# MODUL_RELAIS_8_V101.net
KiCad netlist of a schematic drawn in EAGLE
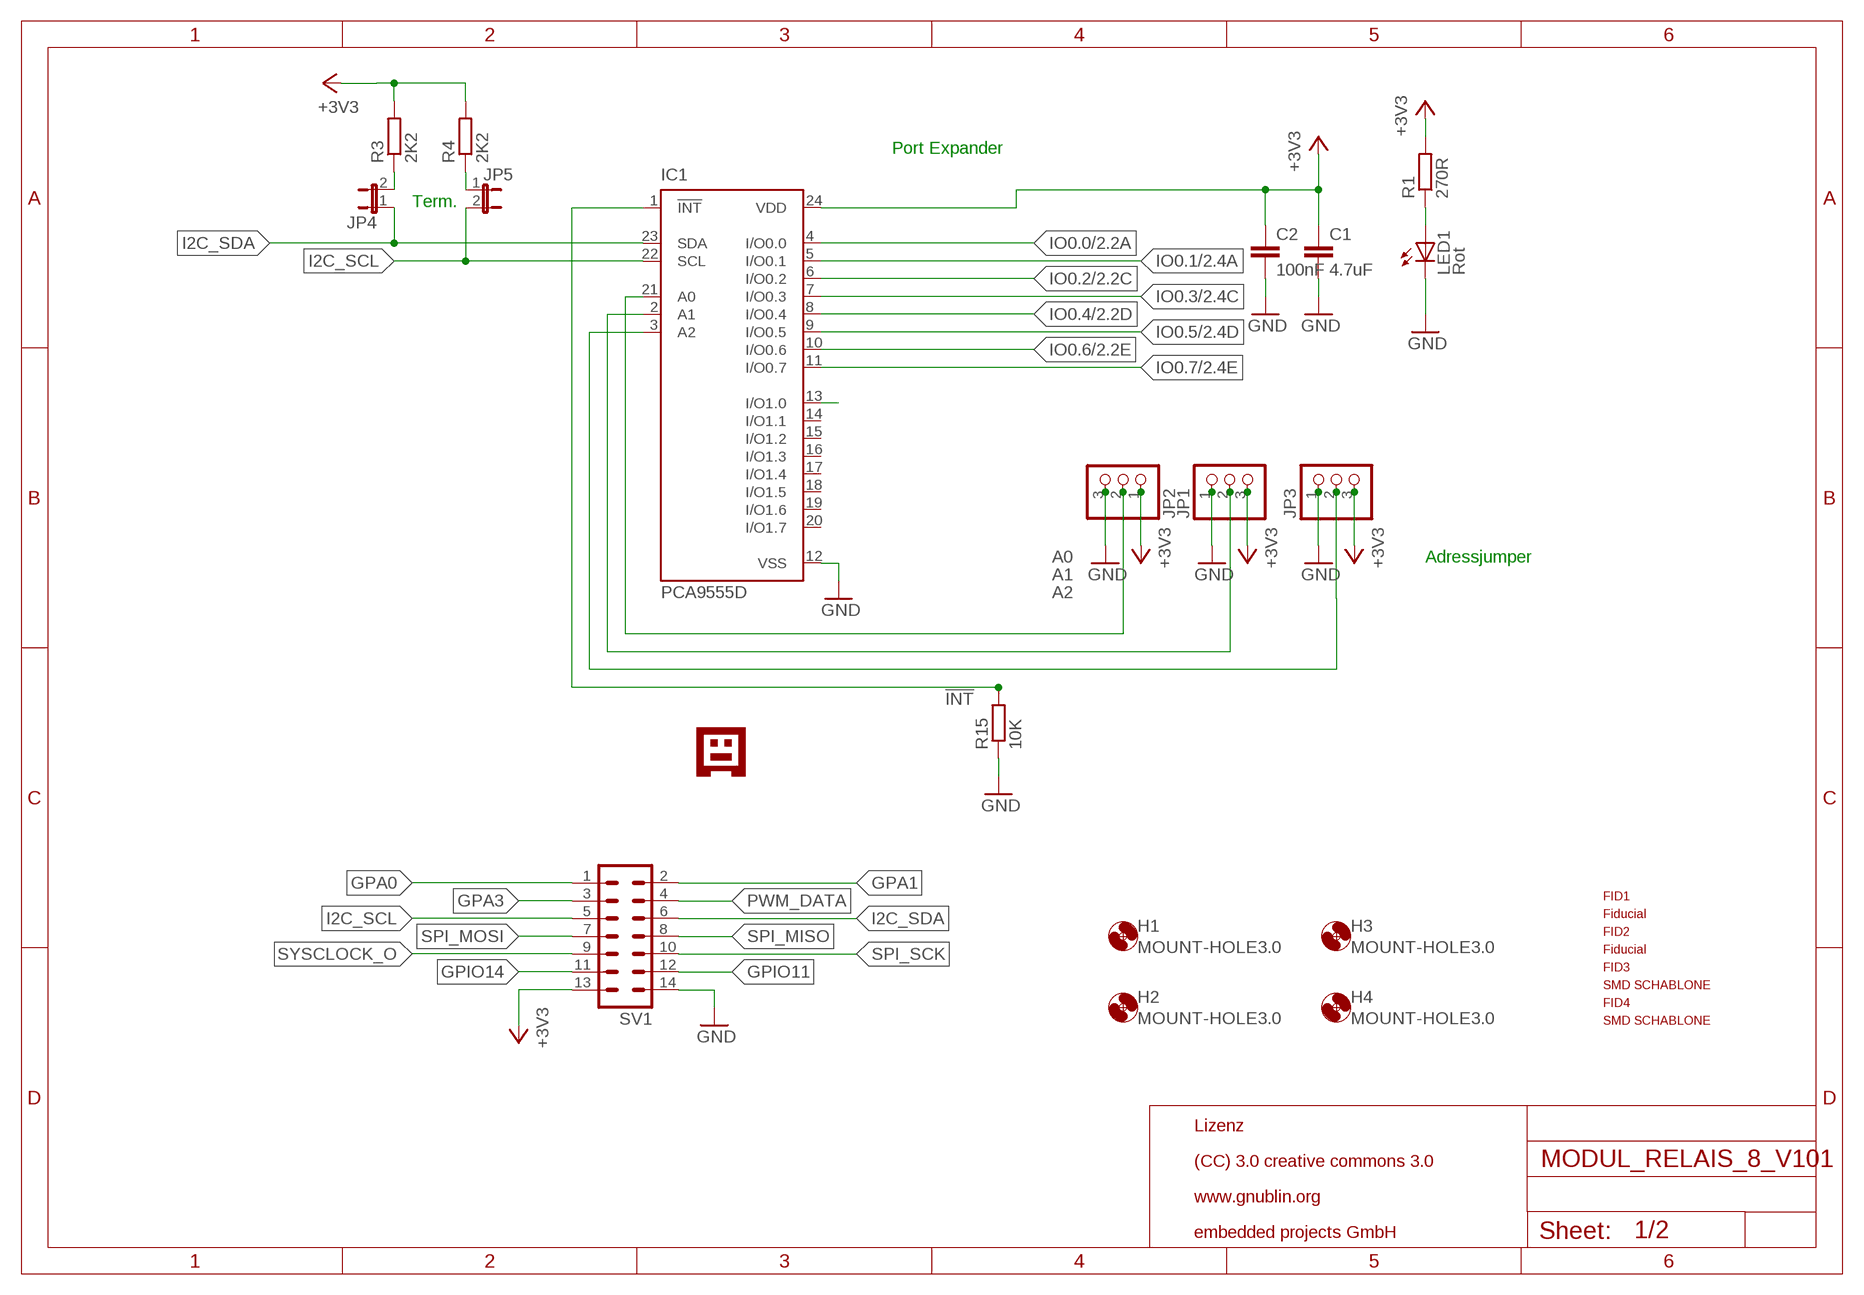
[diagram p0: schematic, sheet 1]
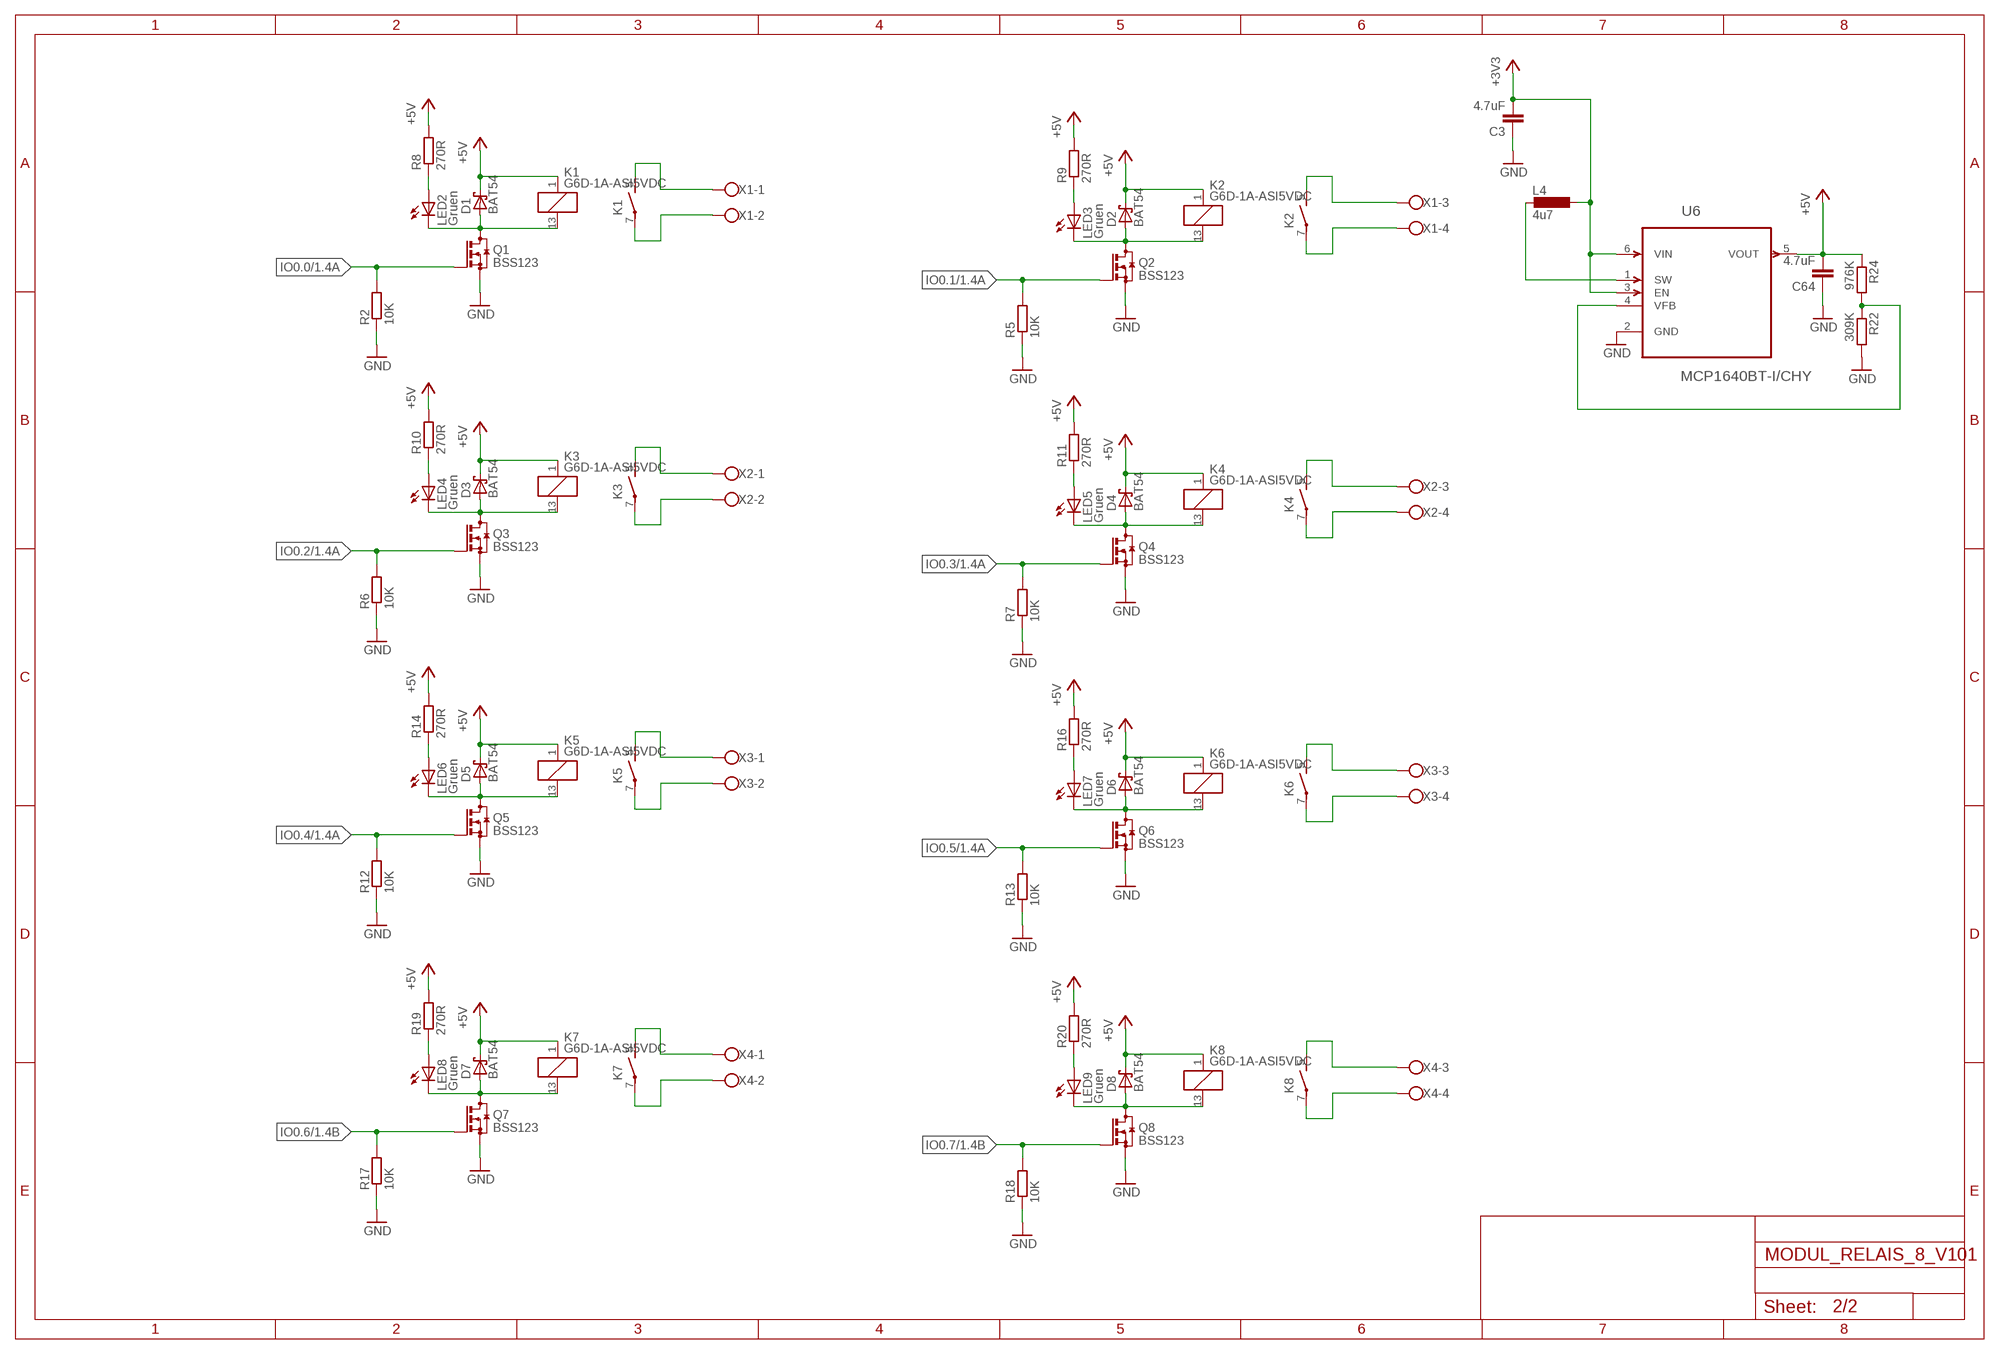
[diagram p1: schematic, sheet 2]

(export (version "E")
  (design (tool "Eeschema 10.0.6"))
  (components
    (comp (ref "C1")
      (value "4.7uF")
      (footprint "eagle-import:C0805")
      (libsource (lib "eagle-import") (part "C-EUC0805"))
    )
    (comp (ref "C2")
      (value "100nF")
      (footprint "eagle-import:C0805")
      (libsource (lib "eagle-import") (part "C-EUC0805"))
    )
    (comp (ref "FID1")
      (value "PASSERMARKEN_FIDUCIAL")
      (footprint "eagle-import:PASSERMARKEN_FIDUCIAL")
      (libsource (lib "eagle-import") (part "PASSERMARKEN_FIDUCIAL"))
    )
    (comp (ref "FID2")
      (value "PASSERMARKEN_FIDUCIAL")
      (footprint "eagle-import:PASSERMARKEN_FIDUCIAL")
      (libsource (lib "eagle-import") (part "PASSERMARKEN_FIDUCIAL"))
    )
    (comp (ref "FID3")
      (value "PASSERMARKEN_FIDUCIAL")
      (footprint "eagle-import:PASSERMARKEN_FIDUCIAL")
      (libsource (lib "eagle-import") (part "SMDSCHABLONE_PASSERMARKEN_FIDUCIAL"))
    )
    (comp (ref "FID4")
      (value "PASSERMARKEN_FIDUCIAL")
      (footprint "eagle-import:PASSERMARKEN_FIDUCIAL")
      (libsource (lib "eagle-import") (part "SMDSCHABLONE_PASSERMARKEN_FIDUCIAL"))
    )
    (comp (ref "H1")
      (value "MOUNT-HOLE3.0")
      (footprint "eagle-import:3,0")
      (libsource (lib "eagle-import") (part "MOUNT-HOLE3.0"))
    )
    (comp (ref "H2")
      (value "MOUNT-HOLE3.0")
      (footprint "eagle-import:3,0")
      (libsource (lib "eagle-import") (part "MOUNT-HOLE3.0"))
    )
    (comp (ref "H3")
      (value "MOUNT-HOLE3.0")
      (footprint "eagle-import:3,0")
      (libsource (lib "eagle-import") (part "MOUNT-HOLE3.0"))
    )
    (comp (ref "H4")
      (value "MOUNT-HOLE3.0")
      (footprint "eagle-import:3,0")
      (libsource (lib "eagle-import") (part "MOUNT-HOLE3.0"))
    )
    (comp (ref "IC1")
      (value "PCA9555D")
      (footprint "eagle-import:SO24")
      (fields (field (name "MPN") "PCA9555DW") (field (name "OC_FARNELL") "8906076"))
      (libsource (lib "eagle-import") (part "PCA9555D"))
    )
    (comp (ref "JP1")
      (value "PINHD-1X3")
      (footprint "eagle-import:1X03")
      (libsource (lib "eagle-import") (part "PINHD-1X3"))
    )
    (comp (ref "JP2")
      (value "PINHD-1X3")
      (footprint "eagle-import:1X03")
      (libsource (lib "eagle-import") (part "PINHD-1X3"))
    )
    (comp (ref "JP3")
      (value "PINHD-1X3")
      (footprint "eagle-import:1X03")
      (libsource (lib "eagle-import") (part "PINHD-1X3"))
    )
    (comp (ref "JP4")
      (value "JP1E")
      (footprint "eagle-import:JP1")
      (libsource (lib "eagle-import") (part "JP1E"))
    )
    (comp (ref "JP5")
      (value "JP1E")
      (footprint "eagle-import:JP1")
      (libsource (lib "eagle-import") (part "JP1E"))
    )
    (comp (ref "LED1")
      (value "Rot")
      (footprint "eagle-import:CHIP-LED0805")
      (libsource (lib "eagle-import") (part "LEDCHIP-LED0805"))
    )
    (comp (ref "R1")
      (value "270R")
      (footprint "eagle-import:R0805")
      (libsource (lib "eagle-import") (part "R-EU_R0805"))
    )
    (comp (ref "R3")
      (value "2K2")
      (footprint "eagle-import:R0805")
      (libsource (lib "eagle-import") (part "R-EU_R0805"))
    )
    (comp (ref "R4")
      (value "2K2")
      (footprint "eagle-import:R0805")
      (libsource (lib "eagle-import") (part "R-EU_R0805"))
    )
    (comp (ref "R15")
      (value "10K")
      (footprint "eagle-import:R0805")
      (libsource (lib "eagle-import") (part "R-EU_R0805"))
    )
    (comp (ref "SV1")
      (value "ML14")
      (footprint "eagle-import:ML14")
      (libsource (lib "eagle-import") (part "ML14"))
    )
    (comp (ref "U$1")
      (value "GNUBLINLOGOSIEB")
      (footprint "eagle-import:GNUSIEBDRUCK")
      (libsource (lib "eagle-import") (part "GNUBLINLOGOSIEB"))
    )
    (comp (ref "C3")
      (value "4.7uF")
      (footprint "eagle-import:C0805")
      (libsource (lib "eagle-import") (part "C-EUC0805"))
    )
    (comp (ref "C64")
      (value "4.7uF")
      (footprint "eagle-import:C0805")
      (libsource (lib "eagle-import") (part "C-EUC0805"))
    )
    (comp (ref "D1")
      (value "BAT54")
      (footprint "eagle-import:DIODE_SOT23")
      (libsource (lib "eagle-import") (part "DIODE_BAT54"))
    )
    (comp (ref "D2")
      (value "BAT54")
      (footprint "eagle-import:DIODE_SOT23")
      (libsource (lib "eagle-import") (part "DIODE_BAT54"))
    )
    (comp (ref "D3")
      (value "BAT54")
      (footprint "eagle-import:DIODE_SOT23")
      (libsource (lib "eagle-import") (part "DIODE_BAT54"))
    )
    (comp (ref "D4")
      (value "BAT54")
      (footprint "eagle-import:DIODE_SOT23")
      (libsource (lib "eagle-import") (part "DIODE_BAT54"))
    )
    (comp (ref "D5")
      (value "BAT54")
      (footprint "eagle-import:DIODE_SOT23")
      (libsource (lib "eagle-import") (part "DIODE_BAT54"))
    )
    (comp (ref "D6")
      (value "BAT54")
      (footprint "eagle-import:DIODE_SOT23")
      (libsource (lib "eagle-import") (part "DIODE_BAT54"))
    )
    (comp (ref "D7")
      (value "BAT54")
      (footprint "eagle-import:DIODE_SOT23")
      (libsource (lib "eagle-import") (part "DIODE_BAT54"))
    )
    (comp (ref "D8")
      (value "BAT54")
      (footprint "eagle-import:DIODE_SOT23")
      (libsource (lib "eagle-import") (part "DIODE_BAT54"))
    )
    (comp (ref "K1")
      (value "G6D-1A-ASI5VDC")
      (footprint "eagle-import:RELAY_G6D")
      (libsource (lib "eagle-import") (part "RELAY_G6D?-1A-ASI5VDC"))
    )
    (comp (ref "K2")
      (value "G6D-1A-ASI5VDC")
      (footprint "eagle-import:RELAY_G6D")
      (libsource (lib "eagle-import") (part "RELAY_G6D?-1A-ASI5VDC"))
    )
    (comp (ref "K3")
      (value "G6D-1A-ASI5VDC")
      (footprint "eagle-import:RELAY_G6D")
      (libsource (lib "eagle-import") (part "RELAY_G6D?-1A-ASI5VDC"))
    )
    (comp (ref "K4")
      (value "G6D-1A-ASI5VDC")
      (footprint "eagle-import:RELAY_G6D")
      (libsource (lib "eagle-import") (part "RELAY_G6D?-1A-ASI5VDC"))
    )
    (comp (ref "K5")
      (value "G6D-1A-ASI5VDC")
      (footprint "eagle-import:RELAY_G6D")
      (libsource (lib "eagle-import") (part "RELAY_G6D?-1A-ASI5VDC"))
    )
    (comp (ref "K6")
      (value "G6D-1A-ASI5VDC")
      (footprint "eagle-import:RELAY_G6D")
      (libsource (lib "eagle-import") (part "RELAY_G6D?-1A-ASI5VDC"))
    )
    (comp (ref "K7")
      (value "G6D-1A-ASI5VDC")
      (footprint "eagle-import:RELAY_G6D")
      (libsource (lib "eagle-import") (part "RELAY_G6D?-1A-ASI5VDC"))
    )
    (comp (ref "K8")
      (value "G6D-1A-ASI5VDC")
      (footprint "eagle-import:RELAY_G6D")
      (libsource (lib "eagle-import") (part "RELAY_G6D?-1A-ASI5VDC"))
    )
    (comp (ref "L4")
      (value "4u7")
      (footprint "eagle-import:PSU3014")
      (libsource (lib "eagle-import") (part "PSU3014"))
    )
    (comp (ref "LED2")
      (value "Gruen")
      (footprint "eagle-import:CHIP-LED0805")
      (libsource (lib "eagle-import") (part "LEDCHIP-LED0805"))
    )
    (comp (ref "LED3")
      (value "Gruen")
      (footprint "eagle-import:CHIP-LED0805")
      (libsource (lib "eagle-import") (part "LEDCHIP-LED0805"))
    )
    (comp (ref "LED4")
      (value "Gruen")
      (footprint "eagle-import:CHIP-LED0805")
      (libsource (lib "eagle-import") (part "LEDCHIP-LED0805"))
    )
    (comp (ref "LED5")
      (value "Gruen")
      (footprint "eagle-import:CHIP-LED0805")
      (libsource (lib "eagle-import") (part "LEDCHIP-LED0805"))
    )
    (comp (ref "LED6")
      (value "Gruen")
      (footprint "eagle-import:CHIP-LED0805")
      (libsource (lib "eagle-import") (part "LEDCHIP-LED0805"))
    )
    (comp (ref "LED7")
      (value "Gruen")
      (footprint "eagle-import:CHIP-LED0805")
      (libsource (lib "eagle-import") (part "LEDCHIP-LED0805"))
    )
    (comp (ref "LED8")
      (value "Gruen")
      (footprint "eagle-import:CHIP-LED0805")
      (libsource (lib "eagle-import") (part "LEDCHIP-LED0805"))
    )
    (comp (ref "LED9")
      (value "Gruen")
      (footprint "eagle-import:CHIP-LED0805")
      (libsource (lib "eagle-import") (part "LEDCHIP-LED0805"))
    )
    (comp (ref "Q1")
      (value "BSS123")
      (footprint "eagle-import:TRANSISTOR-SMALL-SIGNAL_SOT23")
      (libsource (lib "eagle-import") (part "TRANSISTOR-SMALL-SIGNAL_BSS123"))
    )
    (comp (ref "Q2")
      (value "BSS123")
      (footprint "eagle-import:TRANSISTOR-SMALL-SIGNAL_SOT23")
      (libsource (lib "eagle-import") (part "TRANSISTOR-SMALL-SIGNAL_BSS123"))
    )
    (comp (ref "Q3")
      (value "BSS123")
      (footprint "eagle-import:TRANSISTOR-SMALL-SIGNAL_SOT23")
      (libsource (lib "eagle-import") (part "TRANSISTOR-SMALL-SIGNAL_BSS123"))
    )
    (comp (ref "Q4")
      (value "BSS123")
      (footprint "eagle-import:TRANSISTOR-SMALL-SIGNAL_SOT23")
      (libsource (lib "eagle-import") (part "TRANSISTOR-SMALL-SIGNAL_BSS123"))
    )
    (comp (ref "Q5")
      (value "BSS123")
      (footprint "eagle-import:TRANSISTOR-SMALL-SIGNAL_SOT23")
      (libsource (lib "eagle-import") (part "TRANSISTOR-SMALL-SIGNAL_BSS123"))
    )
    (comp (ref "Q6")
      (value "BSS123")
      (footprint "eagle-import:TRANSISTOR-SMALL-SIGNAL_SOT23")
      (libsource (lib "eagle-import") (part "TRANSISTOR-SMALL-SIGNAL_BSS123"))
    )
    (comp (ref "Q7")
      (value "BSS123")
      (footprint "eagle-import:TRANSISTOR-SMALL-SIGNAL_SOT23")
      (libsource (lib "eagle-import") (part "TRANSISTOR-SMALL-SIGNAL_BSS123"))
    )
    (comp (ref "Q8")
      (value "BSS123")
      (footprint "eagle-import:TRANSISTOR-SMALL-SIGNAL_SOT23")
      (libsource (lib "eagle-import") (part "TRANSISTOR-SMALL-SIGNAL_BSS123"))
    )
    (comp (ref "R2")
      (value "10K")
      (footprint "eagle-import:R0805")
      (libsource (lib "eagle-import") (part "R-EU_R0805"))
    )
    (comp (ref "R5")
      (value "10K")
      (footprint "eagle-import:R0805")
      (libsource (lib "eagle-import") (part "R-EU_R0805"))
    )
    (comp (ref "R6")
      (value "10K")
      (footprint "eagle-import:R0805")
      (libsource (lib "eagle-import") (part "R-EU_R0805"))
    )
    (comp (ref "R7")
      (value "10K")
      (footprint "eagle-import:R0805")
      (libsource (lib "eagle-import") (part "R-EU_R0805"))
    )
    (comp (ref "R8")
      (value "270R")
      (footprint "eagle-import:R0805")
      (libsource (lib "eagle-import") (part "R-EU_R0805"))
    )
    (comp (ref "R9")
      (value "270R")
      (footprint "eagle-import:R0805")
      (libsource (lib "eagle-import") (part "R-EU_R0805"))
    )
    (comp (ref "R10")
      (value "270R")
      (footprint "eagle-import:R0805")
      (libsource (lib "eagle-import") (part "R-EU_R0805"))
    )
    (comp (ref "R11")
      (value "270R")
      (footprint "eagle-import:R0805")
      (libsource (lib "eagle-import") (part "R-EU_R0805"))
    )
    (comp (ref "R12")
      (value "10K")
      (footprint "eagle-import:R0805")
      (libsource (lib "eagle-import") (part "R-EU_R0805"))
    )
    (comp (ref "R13")
      (value "10K")
      (footprint "eagle-import:R0805")
      (libsource (lib "eagle-import") (part "R-EU_R0805"))
    )
    (comp (ref "R14")
      (value "270R")
      (footprint "eagle-import:R0805")
      (libsource (lib "eagle-import") (part "R-EU_R0805"))
    )
    (comp (ref "R16")
      (value "270R")
      (footprint "eagle-import:R0805")
      (libsource (lib "eagle-import") (part "R-EU_R0805"))
    )
    (comp (ref "R17")
      (value "10K")
      (footprint "eagle-import:R0805")
      (libsource (lib "eagle-import") (part "R-EU_R0805"))
    )
    (comp (ref "R18")
      (value "10K")
      (footprint "eagle-import:R0805")
      (libsource (lib "eagle-import") (part "R-EU_R0805"))
    )
    (comp (ref "R19")
      (value "270R")
      (footprint "eagle-import:R0805")
      (libsource (lib "eagle-import") (part "R-EU_R0805"))
    )
    (comp (ref "R20")
      (value "270R")
      (footprint "eagle-import:R0805")
      (libsource (lib "eagle-import") (part "R-EU_R0805"))
    )
    (comp (ref "R22")
      (value "309K")
      (footprint "eagle-import:R0805")
      (libsource (lib "eagle-import") (part "R-EU_R0805"))
    )
    (comp (ref "R24")
      (value "976K")
      (footprint "eagle-import:R0805")
      (libsource (lib "eagle-import") (part "R-EU_R0805"))
    )
    (comp (ref "U6")
      (value "MCP1640BT-I/CHY")
      (footprint "eagle-import:SOT95P270X145-6N")
      (libsource (lib "eagle-import") (part "MCP1640BT-I/CHY"))
    )
    (comp (ref "X1")
      (value "W237-04P")
      (footprint "eagle-import:W237-4P")
      (libsource (lib "eagle-import") (part "W237-04P"))
    )
    (comp (ref "X2")
      (value "W237-04P")
      (footprint "eagle-import:W237-4P")
      (libsource (lib "eagle-import") (part "W237-04P"))
    )
    (comp (ref "X3")
      (value "W237-04P")
      (footprint "eagle-import:W237-4P")
      (libsource (lib "eagle-import") (part "W237-04P"))
    )
    (comp (ref "X4")
      (value "W237-04P")
      (footprint "eagle-import:W237-4P")
      (libsource (lib "eagle-import") (part "W237-04P"))
    )
  )
  (nets
    (net (code "1") (name "+3V3") (class "Default")
      (node (ref "C1") (pin "1") (pinfunction "1_1") (pintype "passive"))
      (node (ref "C2") (pin "1") (pinfunction "1_1") (pintype "passive"))
      (node (ref "C3") (pin "2") (pinfunction "2_2") (pintype "passive"))
      (node (ref "IC1") (pin "24") (pinfunction "VDD_24") (pintype "power_in"))
      (node (ref "JP1") (pin "3") (pinfunction "3_3") (pintype "passive"))
      (node (ref "JP2") (pin "1") (pinfunction "1_1") (pintype "passive"))
      (node (ref "JP3") (pin "3") (pinfunction "3_3") (pintype "passive"))
      (node (ref "L4") (pin "2") (pinfunction "2_2") (pintype "passive"))
      (node (ref "R1") (pin "2") (pinfunction "2_2") (pintype "passive"))
      (node (ref "R3") (pin "2") (pinfunction "2_2") (pintype "passive"))
      (node (ref "R4") (pin "2") (pinfunction "2_2") (pintype "passive"))
      (node (ref "SV1") (pin "13") (pinfunction "13_13") (pintype "passive"))
      (node (ref "U6") (pin "3") (pinfunction "EN_3") (pintype "input"))
      (node (ref "U6") (pin "6") (pinfunction "VIN_6") (pintype "input"))
    )
    (net (code "2") (name "+5V") (class "Default")
      (node (ref "C64") (pin "2") (pinfunction "2_2") (pintype "passive"))
      (node (ref "D1") (pin "3") (pinfunction "C_3") (pintype "passive"))
      (node (ref "D2") (pin "3") (pinfunction "C_3") (pintype "passive"))
      (node (ref "D3") (pin "3") (pinfunction "C_3") (pintype "passive"))
      (node (ref "D4") (pin "3") (pinfunction "C_3") (pintype "passive"))
      (node (ref "D5") (pin "3") (pinfunction "C_3") (pintype "passive"))
      (node (ref "D6") (pin "3") (pinfunction "C_3") (pintype "passive"))
      (node (ref "D7") (pin "3") (pinfunction "C_3") (pintype "passive"))
      (node (ref "D8") (pin "3") (pinfunction "C_3") (pintype "passive"))
      (node (ref "K1") (pin "1") (pinfunction "1_1") (pintype "passive"))
      (node (ref "K2") (pin "1") (pinfunction "1_1") (pintype "passive"))
      (node (ref "K3") (pin "1") (pinfunction "1_1") (pintype "passive"))
      (node (ref "K4") (pin "1") (pinfunction "1_1") (pintype "passive"))
      (node (ref "K5") (pin "1") (pinfunction "1_1") (pintype "passive"))
      (node (ref "K6") (pin "1") (pinfunction "1_1") (pintype "passive"))
      (node (ref "K7") (pin "1") (pinfunction "1_1") (pintype "passive"))
      (node (ref "K8") (pin "1") (pinfunction "1_1") (pintype "passive"))
      (node (ref "R10") (pin "2") (pinfunction "2_2") (pintype "passive"))
      (node (ref "R11") (pin "2") (pinfunction "2_2") (pintype "passive"))
      (node (ref "R14") (pin "2") (pinfunction "2_2") (pintype "passive"))
      (node (ref "R16") (pin "2") (pinfunction "2_2") (pintype "passive"))
      (node (ref "R19") (pin "2") (pinfunction "2_2") (pintype "passive"))
      (node (ref "R20") (pin "2") (pinfunction "2_2") (pintype "passive"))
      (node (ref "R24") (pin "1") (pinfunction "1_1") (pintype "passive"))
      (node (ref "R8") (pin "2") (pinfunction "2_2") (pintype "passive"))
      (node (ref "R9") (pin "2") (pinfunction "2_2") (pintype "passive"))
      (node (ref "U6") (pin "5") (pinfunction "VOUT_5") (pintype "output"))
    )
    (net (code "3") (name "A0") (class "Default")
      (node (ref "IC1") (pin "21") (pinfunction "A0_21") (pintype "input"))
      (node (ref "JP2") (pin "2") (pinfunction "2_2") (pintype "passive"))
    )
    (net (code "4") (name "A1") (class "Default")
      (node (ref "IC1") (pin "2") (pinfunction "A1_2") (pintype "input"))
      (node (ref "JP1") (pin "2") (pinfunction "2_2") (pintype "passive"))
    )
    (net (code "5") (name "A2") (class "Default")
      (node (ref "IC1") (pin "3") (pinfunction "A2_3") (pintype "input"))
      (node (ref "JP3") (pin "2") (pinfunction "2_2") (pintype "passive"))
    )
    (net (code "6") (name "GND") (class "Default")
      (node (ref "C1") (pin "2") (pinfunction "2_2") (pintype "passive"))
      (node (ref "C2") (pin "2") (pinfunction "2_2") (pintype "passive"))
      (node (ref "C3") (pin "1") (pinfunction "1_1") (pintype "passive"))
      (node (ref "C64") (pin "1") (pinfunction "1_1") (pintype "passive"))
      (node (ref "IC1") (pin "12") (pinfunction "VSS_12") (pintype "power_in"))
      (node (ref "JP1") (pin "1") (pinfunction "1_1") (pintype "passive"))
      (node (ref "JP2") (pin "3") (pinfunction "3_3") (pintype "passive"))
      (node (ref "JP3") (pin "1") (pinfunction "1_1") (pintype "passive"))
      (node (ref "LED1") (pin "C") (pinfunction "C_C") (pintype "passive"))
      (node (ref "Q1") (pin "2") (pinfunction "S_2") (pintype "passive"))
      (node (ref "Q2") (pin "2") (pinfunction "S_2") (pintype "passive"))
      (node (ref "Q3") (pin "2") (pinfunction "S_2") (pintype "passive"))
      (node (ref "Q4") (pin "2") (pinfunction "S_2") (pintype "passive"))
      (node (ref "Q5") (pin "2") (pinfunction "S_2") (pintype "passive"))
      (node (ref "Q6") (pin "2") (pinfunction "S_2") (pintype "passive"))
      (node (ref "Q7") (pin "2") (pinfunction "S_2") (pintype "passive"))
      (node (ref "Q8") (pin "2") (pinfunction "S_2") (pintype "passive"))
      (node (ref "R12") (pin "1") (pinfunction "1_1") (pintype "passive"))
      (node (ref "R13") (pin "1") (pinfunction "1_1") (pintype "passive"))
      (node (ref "R15") (pin "1") (pinfunction "1_1") (pintype "passive"))
      (node (ref "R17") (pin "1") (pinfunction "1_1") (pintype "passive"))
      (node (ref "R18") (pin "1") (pinfunction "1_1") (pintype "passive"))
      (node (ref "R2") (pin "1") (pinfunction "1_1") (pintype "passive"))
      (node (ref "R22") (pin "2") (pinfunction "2_2") (pintype "passive"))
      (node (ref "R5") (pin "1") (pinfunction "1_1") (pintype "passive"))
      (node (ref "R6") (pin "1") (pinfunction "1_1") (pintype "passive"))
      (node (ref "R7") (pin "1") (pinfunction "1_1") (pintype "passive"))
      (node (ref "SV1") (pin "14") (pinfunction "14_14") (pintype "passive"))
      (node (ref "U6") (pin "2") (pinfunction "GND_2") (pintype "passive"))
    )
    (net (code "7") (name "GPA0") (class "Default")
      (node (ref "SV1") (pin "1") (pinfunction "1_1") (pintype "passive"))
    )
    (net (code "8") (name "GPA1") (class "Default")
      (node (ref "SV1") (pin "2") (pinfunction "2_2") (pintype "passive"))
    )
    (net (code "9") (name "GPA3") (class "Default")
      (node (ref "SV1") (pin "3") (pinfunction "3_3") (pintype "passive"))
    )
    (net (code "10") (name "GPIO11") (class "Default")
      (node (ref "SV1") (pin "12") (pinfunction "12_12") (pintype "passive"))
    )
    (net (code "11") (name "GPIO14") (class "Default")
      (node (ref "SV1") (pin "11") (pinfunction "11_11") (pintype "passive"))
    )
    (net (code "12") (name "I2C_SCL") (class "Default")
      (node (ref "IC1") (pin "22") (pinfunction "SCL_22") (pintype "input"))
      (node (ref "JP5") (pin "2") (pinfunction "2_2") (pintype "passive"))
      (node (ref "SV1") (pin "5") (pinfunction "5_5") (pintype "passive"))
    )
    (net (code "13") (name "I2C_SDA") (class "Default")
      (node (ref "IC1") (pin "23") (pinfunction "SDA_23") (pintype "bidirectional"))
      (node (ref "JP4") (pin "1") (pinfunction "1_1") (pintype "passive"))
      (node (ref "SV1") (pin "6") (pinfunction "6_6") (pintype "passive"))
    )
    (net (code "14") (name "IO0.0") (class "Default")
      (node (ref "IC1") (pin "4") (pinfunction "I/O0.0_4") (pintype "bidirectional"))
      (node (ref "Q1") (pin "1") (pinfunction "G_1") (pintype "passive"))
      (node (ref "R2") (pin "2") (pinfunction "2_2") (pintype "passive"))
    )
    (net (code "15") (name "IO0.1") (class "Default")
      (node (ref "IC1") (pin "5") (pinfunction "I/O0.1_5") (pintype "bidirectional"))
      (node (ref "Q2") (pin "1") (pinfunction "G_1") (pintype "passive"))
      (node (ref "R5") (pin "2") (pinfunction "2_2") (pintype "passive"))
    )
    (net (code "16") (name "IO0.2") (class "Default")
      (node (ref "IC1") (pin "6") (pinfunction "I/O0.2_6") (pintype "bidirectional"))
      (node (ref "Q3") (pin "1") (pinfunction "G_1") (pintype "passive"))
      (node (ref "R6") (pin "2") (pinfunction "2_2") (pintype "passive"))
    )
    (net (code "17") (name "IO0.3") (class "Default")
      (node (ref "IC1") (pin "7") (pinfunction "I/O0.3_7") (pintype "bidirectional"))
      (node (ref "Q4") (pin "1") (pinfunction "G_1") (pintype "passive"))
      (node (ref "R7") (pin "2") (pinfunction "2_2") (pintype "passive"))
    )
    (net (code "18") (name "IO0.4") (class "Default")
      (node (ref "IC1") (pin "8") (pinfunction "I/O0.4_8") (pintype "bidirectional"))
      (node (ref "Q5") (pin "1") (pinfunction "G_1") (pintype "passive"))
      (node (ref "R12") (pin "2") (pinfunction "2_2") (pintype "passive"))
    )
    (net (code "19") (name "IO0.5") (class "Default")
      (node (ref "IC1") (pin "9") (pinfunction "I/O0.5_9") (pintype "bidirectional"))
      (node (ref "Q6") (pin "1") (pinfunction "G_1") (pintype "passive"))
      (node (ref "R13") (pin "2") (pinfunction "2_2") (pintype "passive"))
    )
    (net (code "20") (name "IO0.6") (class "Default")
      (node (ref "IC1") (pin "10") (pinfunction "I/O0.6_10") (pintype "bidirectional"))
      (node (ref "Q7") (pin "1") (pinfunction "G_1") (pintype "passive"))
      (node (ref "R17") (pin "2") (pinfunction "2_2") (pintype "passive"))
    )
    (net (code "21") (name "IO0.7") (class "Default")
      (node (ref "IC1") (pin "11") (pinfunction "I/O0.7_11") (pintype "bidirectional"))
      (node (ref "Q8") (pin "1") (pinfunction "G_1") (pintype "passive"))
      (node (ref "R18") (pin "2") (pinfunction "2_2") (pintype "passive"))
    )
    (net (code "22") (name "Net-(D1-A)") (class "Default")
      (node (ref "D1") (pin "1") (pinfunction "A_1") (pintype "passive"))
      (node (ref "K1") (pin "13") (pinfunction "2_13") (pintype "passive"))
      (node (ref "LED2") (pin "C") (pinfunction "C_C") (pintype "passive"))
      (node (ref "Q1") (pin "3") (pinfunction "D_3") (pintype "passive"))
    )
    (net (code "23") (name "Net-(D2-A)") (class "Default")
      (node (ref "D2") (pin "1") (pinfunction "A_1") (pintype "passive"))
      (node (ref "K2") (pin "13") (pinfunction "2_13") (pintype "passive"))
      (node (ref "LED3") (pin "C") (pinfunction "C_C") (pintype "passive"))
      (node (ref "Q2") (pin "3") (pinfunction "D_3") (pintype "passive"))
    )
    (net (code "24") (name "Net-(D3-A)") (class "Default")
      (node (ref "D3") (pin "1") (pinfunction "A_1") (pintype "passive"))
      (node (ref "K3") (pin "13") (pinfunction "2_13") (pintype "passive"))
      (node (ref "LED4") (pin "C") (pinfunction "C_C") (pintype "passive"))
      (node (ref "Q3") (pin "3") (pinfunction "D_3") (pintype "passive"))
    )
    (net (code "25") (name "Net-(D4-A)") (class "Default")
      (node (ref "D4") (pin "1") (pinfunction "A_1") (pintype "passive"))
      (node (ref "K4") (pin "13") (pinfunction "2_13") (pintype "passive"))
      (node (ref "LED5") (pin "C") (pinfunction "C_C") (pintype "passive"))
      (node (ref "Q4") (pin "3") (pinfunction "D_3") (pintype "passive"))
    )
    (net (code "26") (name "Net-(D5-A)") (class "Default")
      (node (ref "D5") (pin "1") (pinfunction "A_1") (pintype "passive"))
      (node (ref "K5") (pin "13") (pinfunction "2_13") (pintype "passive"))
      (node (ref "LED6") (pin "C") (pinfunction "C_C") (pintype "passive"))
      (node (ref "Q5") (pin "3") (pinfunction "D_3") (pintype "passive"))
    )
    (net (code "27") (name "Net-(D6-A)") (class "Default")
      (node (ref "D6") (pin "1") (pinfunction "A_1") (pintype "passive"))
      (node (ref "K6") (pin "13") (pinfunction "2_13") (pintype "passive"))
      (node (ref "LED7") (pin "C") (pinfunction "C_C") (pintype "passive"))
      (node (ref "Q6") (pin "3") (pinfunction "D_3") (pintype "passive"))
    )
    (net (code "28") (name "Net-(D7-A)") (class "Default")
      (node (ref "D7") (pin "1") (pinfunction "A_1") (pintype "passive"))
      (node (ref "K7") (pin "13") (pinfunction "2_13") (pintype "passive"))
      (node (ref "LED8") (pin "C") (pinfunction "C_C") (pintype "passive"))
      (node (ref "Q7") (pin "3") (pinfunction "D_3") (pintype "passive"))
    )
    (net (code "29") (name "Net-(D8-A)") (class "Default")
      (node (ref "D8") (pin "1") (pinfunction "A_1") (pintype "passive"))
      (node (ref "K8") (pin "13") (pinfunction "2_13") (pintype "passive"))
      (node (ref "LED9") (pin "C") (pinfunction "C_C") (pintype "passive"))
      (node (ref "Q8") (pin "3") (pinfunction "D_3") (pintype "passive"))
    )
    (net (code "30") (name "Net-(JP4-Pad2)") (class "Default")
      (node (ref "JP4") (pin "2") (pinfunction "2_2") (pintype "passive"))
      (node (ref "R3") (pin "1") (pinfunction "1_1") (pintype "passive"))
    )
    (net (code "31") (name "Net-(JP5-Pad1)") (class "Default")
      (node (ref "JP5") (pin "1") (pinfunction "1_1") (pintype "passive"))
      (node (ref "R4") (pin "1") (pinfunction "1_1") (pintype "passive"))
    )
    (net (code "32") (name "Net-(K1B-P)") (class "Default")
      (node (ref "K1") (pin "7") (pinfunction "P_7") (pintype "passive"))
      (node (ref "X1") (pin "2") (pinfunction "KL_2") (pintype "passive"))
    )
    (net (code "33") (name "Net-(K1B-S)") (class "Default")
      (node (ref "K1") (pin "5") (pinfunction "S_5") (pintype "passive"))
      (node (ref "X1") (pin "1") (pinfunction "KL_1") (pintype "passive"))
    )
    (net (code "34") (name "Net-(K2B-P)") (class "Default")
      (node (ref "K2") (pin "7") (pinfunction "P_7") (pintype "passive"))
      (node (ref "X1") (pin "4") (pinfunction "KL_4") (pintype "passive"))
    )
    (net (code "35") (name "Net-(K2B-S)") (class "Default")
      (node (ref "K2") (pin "5") (pinfunction "S_5") (pintype "passive"))
      (node (ref "X1") (pin "3") (pinfunction "KL_3") (pintype "passive"))
    )
    (net (code "36") (name "Net-(K3B-P)") (class "Default")
      (node (ref "K3") (pin "7") (pinfunction "P_7") (pintype "passive"))
      (node (ref "X2") (pin "2") (pinfunction "KL_2") (pintype "passive"))
    )
    (net (code "37") (name "Net-(K3B-S)") (class "Default")
      (node (ref "K3") (pin "5") (pinfunction "S_5") (pintype "passive"))
      (node (ref "X2") (pin "1") (pinfunction "KL_1") (pintype "passive"))
    )
    (net (code "38") (name "Net-(K4B-P)") (class "Default")
      (node (ref "K4") (pin "7") (pinfunction "P_7") (pintype "passive"))
      (node (ref "X2") (pin "4") (pinfunction "KL_4") (pintype "passive"))
    )
    (net (code "39") (name "Net-(K4B-S)") (class "Default")
      (node (ref "K4") (pin "5") (pinfunction "S_5") (pintype "passive"))
      (node (ref "X2") (pin "3") (pinfunction "KL_3") (pintype "passive"))
    )
    (net (code "40") (name "Net-(K5B-P)") (class "Default")
      (node (ref "K5") (pin "7") (pinfunction "P_7") (pintype "passive"))
      (node (ref "X3") (pin "2") (pinfunction "KL_2") (pintype "passive"))
    )
    (net (code "41") (name "Net-(K5B-S)") (class "Default")
      (node (ref "K5") (pin "5") (pinfunction "S_5") (pintype "passive"))
      (node (ref "X3") (pin "1") (pinfunction "KL_1") (pintype "passive"))
    )
    (net (code "42") (name "Net-(K6B-P)") (class "Default")
      (node (ref "K6") (pin "7") (pinfunction "P_7") (pintype "passive"))
      (node (ref "X3") (pin "4") (pinfunction "KL_4") (pintype "passive"))
    )
    (net (code "43") (name "Net-(K6B-S)") (class "Default")
      (node (ref "K6") (pin "5") (pinfunction "S_5") (pintype "passive"))
      (node (ref "X3") (pin "3") (pinfunction "KL_3") (pintype "passive"))
    )
    (net (code "44") (name "Net-(K7B-P)") (class "Default")
      (node (ref "K7") (pin "7") (pinfunction "P_7") (pintype "passive"))
      (node (ref "X4") (pin "2") (pinfunction "KL_2") (pintype "passive"))
    )
    (net (code "45") (name "Net-(K7B-S)") (class "Default")
      (node (ref "K7") (pin "5") (pinfunction "S_5") (pintype "passive"))
      (node (ref "X4") (pin "1") (pinfunction "KL_1") (pintype "passive"))
    )
    (net (code "46") (name "Net-(K8B-P)") (class "Default")
      (node (ref "K8") (pin "7") (pinfunction "P_7") (pintype "passive"))
      (node (ref "X4") (pin "4") (pinfunction "KL_4") (pintype "passive"))
    )
    (net (code "47") (name "Net-(K8B-S)") (class "Default")
      (node (ref "K8") (pin "5") (pinfunction "S_5") (pintype "passive"))
      (node (ref "X4") (pin "3") (pinfunction "KL_3") (pintype "passive"))
    )
    (net (code "48") (name "Net-(LED1-PadA)") (class "Default")
      (node (ref "LED1") (pin "A") (pinfunction "A_A") (pintype "passive"))
      (node (ref "R1") (pin "1") (pinfunction "1_1") (pintype "passive"))
    )
    (net (code "49") (name "Net-(LED2-PadA)") (class "Default")
      (node (ref "LED2") (pin "A") (pinfunction "A_A") (pintype "passive"))
      (node (ref "R8") (pin "1") (pinfunction "1_1") (pintype "passive"))
    )
    (net (code "50") (name "Net-(LED3-PadA)") (class "Default")
      (node (ref "LED3") (pin "A") (pinfunction "A_A") (pintype "passive"))
      (node (ref "R9") (pin "1") (pinfunction "1_1") (pintype "passive"))
    )
    (net (code "51") (name "Net-(LED4-PadA)") (class "Default")
      (node (ref "LED4") (pin "A") (pinfunction "A_A") (pintype "passive"))
      (node (ref "R10") (pin "1") (pinfunction "1_1") (pintype "passive"))
    )
    (net (code "52") (name "Net-(LED5-PadA)") (class "Default")
      (node (ref "LED5") (pin "A") (pinfunction "A_A") (pintype "passive"))
      (node (ref "R11") (pin "1") (pinfunction "1_1") (pintype "passive"))
    )
    (net (code "53") (name "Net-(LED6-PadA)") (class "Default")
      (node (ref "LED6") (pin "A") (pinfunction "A_A") (pintype "passive"))
      (node (ref "R14") (pin "1") (pinfunction "1_1") (pintype "passive"))
    )
    (net (code "54") (name "Net-(LED7-PadA)") (class "Default")
      (node (ref "LED7") (pin "A") (pinfunction "A_A") (pintype "passive"))
      (node (ref "R16") (pin "1") (pinfunction "1_1") (pintype "passive"))
    )
    (net (code "55") (name "Net-(LED8-PadA)") (class "Default")
      (node (ref "LED8") (pin "A") (pinfunction "A_A") (pintype "passive"))
      (node (ref "R19") (pin "1") (pinfunction "1_1") (pintype "passive"))
    )
    (net (code "56") (name "Net-(LED9-PadA)") (class "Default")
      (node (ref "LED9") (pin "A") (pinfunction "A_A") (pintype "passive"))
      (node (ref "R20") (pin "1") (pinfunction "1_1") (pintype "passive"))
    )
    (net (code "57") (name "Net-(U6-SW)") (class "Default")
      (node (ref "L4") (pin "1") (pinfunction "1_1") (pintype "passive"))
      (node (ref "U6") (pin "1") (pinfunction "SW_1") (pintype "input"))
    )
    (net (code "58") (name "Net-(U6-VFB)") (class "Default")
      (node (ref "R22") (pin "1") (pinfunction "1_1") (pintype "passive"))
      (node (ref "R24") (pin "2") (pinfunction "2_2") (pintype "passive"))
      (node (ref "U6") (pin "4") (pinfunction "VFB_4") (pintype "input"))
    )
    (net (code "59") (name "PWM_DATA") (class "Default")
      (node (ref "SV1") (pin "4") (pinfunction "4_4") (pintype "passive"))
    )
    (net (code "60") (name "SPI_MISO") (class "Default")
      (node (ref "SV1") (pin "8") (pinfunction "8_8") (pintype "passive"))
    )
    (net (code "61") (name "SPI_MOSI") (class "Default")
      (node (ref "SV1") (pin "7") (pinfunction "7_7") (pintype "passive"))
    )
    (net (code "62") (name "SPI_SCK") (class "Default")
      (node (ref "SV1") (pin "10") (pinfunction "10_10") (pintype "passive"))
    )
    (net (code "63") (name "SYSCLOCK_O") (class "Default")
      (node (ref "SV1") (pin "9") (pinfunction "9_9") (pintype "passive"))
    )
    (net (code "64") (name "unconnected-(IC1-I{slash}O1.0-Pad13)") (class "Default")
      (node (ref "IC1") (pin "13") (pinfunction "I/O1.0_13") (pintype "bidirectional"))
    )
    (net (code "65") (name "unconnected-(IC1-I{slash}O1.1-Pad14)") (class "Default")
      (node (ref "IC1") (pin "14") (pinfunction "I/O1.1_14") (pintype "bidirectional"))
    )
    (net (code "66") (name "unconnected-(IC1-I{slash}O1.2-Pad15)") (class "Default")
      (node (ref "IC1") (pin "15") (pinfunction "I/O1.2_15") (pintype "bidirectional"))
    )
    (net (code "67") (name "unconnected-(IC1-I{slash}O1.3-Pad16)") (class "Default")
      (node (ref "IC1") (pin "16") (pinfunction "I/O1.3_16") (pintype "bidirectional"))
    )
    (net (code "68") (name "unconnected-(IC1-I{slash}O1.4-Pad17)") (class "Default")
      (node (ref "IC1") (pin "17") (pinfunction "I/O1.4_17") (pintype "bidirectional"))
    )
    (net (code "69") (name "unconnected-(IC1-I{slash}O1.5-Pad18)") (class "Default")
      (node (ref "IC1") (pin "18") (pinfunction "I/O1.5_18") (pintype "bidirectional"))
    )
    (net (code "70") (name "unconnected-(IC1-I{slash}O1.6-Pad19)") (class "Default")
      (node (ref "IC1") (pin "19") (pinfunction "I/O1.6_19") (pintype "bidirectional"))
    )
    (net (code "71") (name "unconnected-(IC1-I{slash}O1.7-Pad20)") (class "Default")
      (node (ref "IC1") (pin "20") (pinfunction "I/O1.7_20") (pintype "bidirectional"))
    )
    (net (code "72") (name "~{INT}") (class "Default")
      (node (ref "IC1") (pin "1") (pinfunction "~{INT}_1") (pintype "output"))
      (node (ref "R15") (pin "2") (pinfunction "2_2") (pintype "passive"))
    )
  )
)
